# WeightPuzzle.net
KiCad netlist of a schematic drawn in Altium Designer
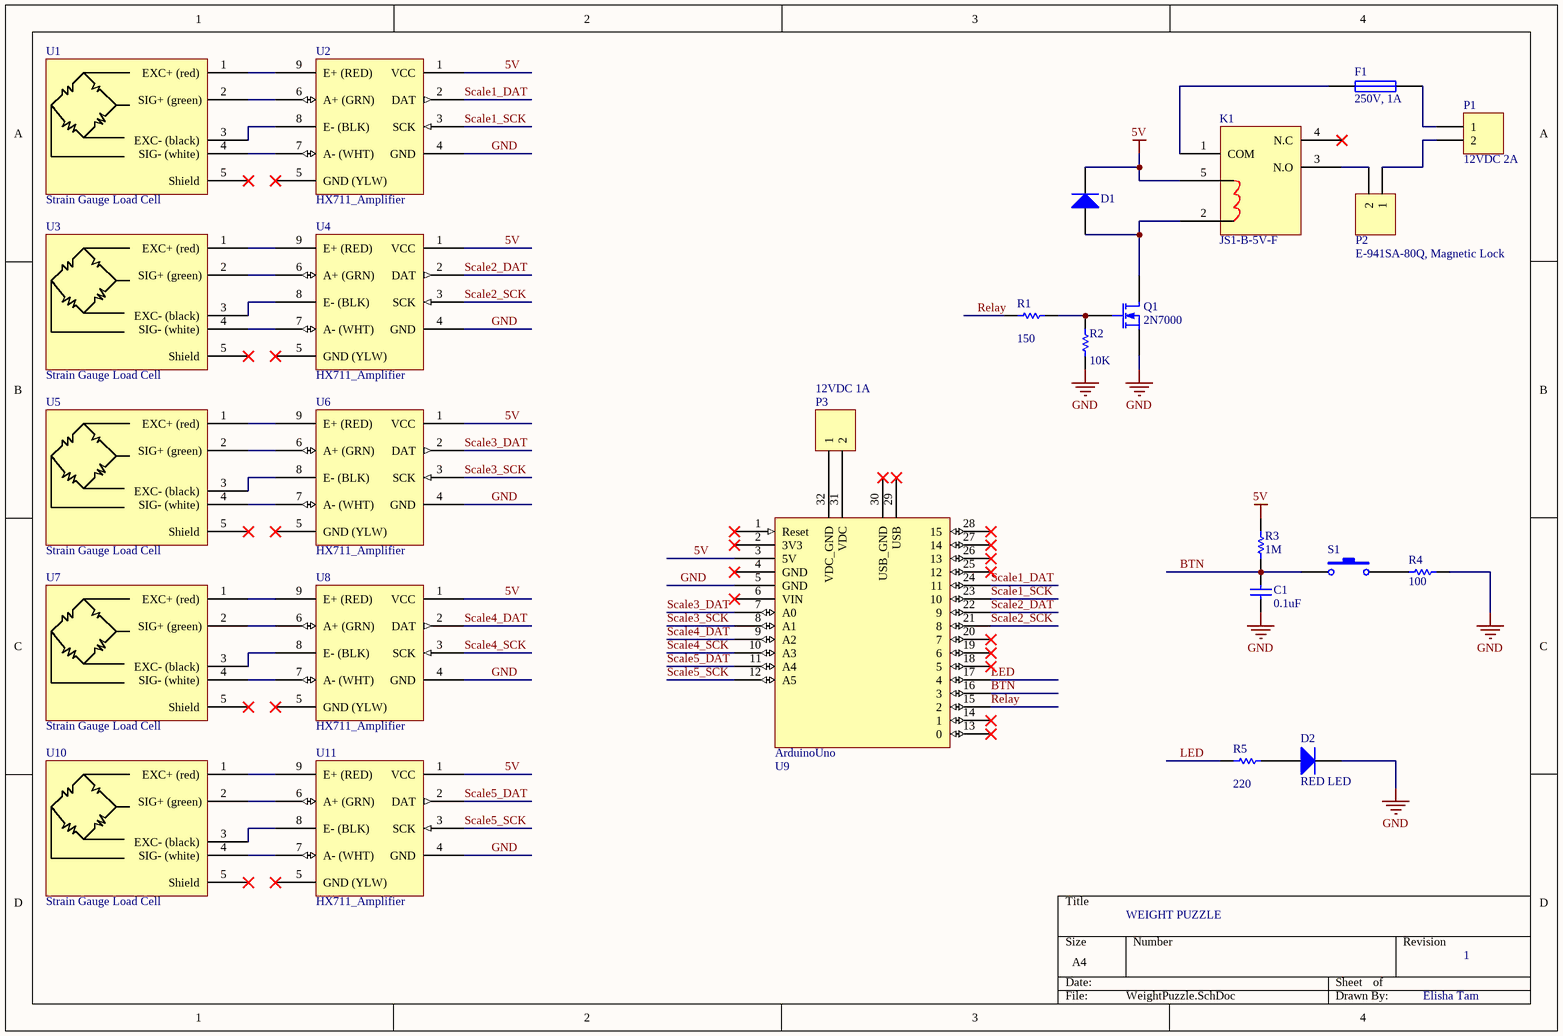
[diagram p0: WeightPuzzle.SchDoc]

(export (version "E")
  (design (tool "Eeschema 10.0.6"))
  (components
    (comp (ref "C1")
      (value "0.1uF")
      (footprint "RAD-0.3")
      (description "Capacitor")
      (fields (field (name "PUBLISHER") "Altium Limited"))
      (libsource (lib "Miscellaneous Devices") (part "Cap"))
    )
    (comp (ref "D1")
      (value "Diode")
      (footprint "SMC")
      (description "Default Diode")
      (fields (field (name "PUBLISHER") "Altium Limited"))
      (libsource (lib "Miscellaneous Devices") (part "Diode"))
    )
    (comp (ref "D2")
      (value "RED LED")
      (footprint "SMC")
      (description "Default Diode")
      (fields (field (name "PUBLISHER") "Altium Limited"))
      (libsource (lib "Miscellaneous Devices") (part "Diode"))
    )
    (comp (ref "F1")
      (value "250V, 1A")
      (footprint "PIN-W2/E2.8")
      (description "Fuse")
      (fields (field (name "PUBLISHER") "Altium Limited"))
      (libsource (lib "Miscellaneous Devices") (part "Fuse 1"))
    )
    (comp (ref "K1")
      (value "JS1-B-5V-F")
      (description "SPDT Relay 10A250VAC 10A 125VAC 5V")
      (libsource (lib "ElishaComponentsAltiumLibrary") (part "JS1-B-5V-F"))
    )
    (comp (ref "P1")
      (value "12VDC 2A")
      (footprint "HDR1X2")
      (description "Header, 2-Pin")
      (fields (field (name "PUBLISHER") "Altium Limited"))
      (libsource (lib "Miscellaneous Connectors") (part "Header 2"))
    )
    (comp (ref "P2")
      (value "E-941SA-80Q, Magnetic Lock")
      (footprint "HDR1X2")
      (description "Seco-Larm E-941SA-80Q Mini Maglock, 80 lb.")
      (fields (field (name "PUBLISHER") "Altium Limited"))
      (libsource (lib "") (part "Header 2_2"))
    )
    (comp (ref "P3")
      (value "12VDC 1A")
      (footprint "HDR1X2")
      (description "12V DC Adapter")
      (fields (field (name "PUBLISHER") "Altium Limited"))
      (libsource (lib "") (part "Header 2_1"))
    )
    (comp (ref "Q1")
      (value "2N7000")
      (footprint "E3")
      (description "N-Channel MOSFET")
      (fields (field (name "PUBLISHER") "Altium Limited"))
      (libsource (lib "Miscellaneous Devices") (part "MOSFET-N"))
    )
    (comp (ref "R1")
      (value "150")
      (footprint "AXIAL-0.3")
      (description "Resistor")
      (fields (field (name "Comment") "Res1") (field (name "PUBLISHER") "Altium Limited"))
      (libsource (lib "Miscellaneous Devices") (part "Res1"))
    )
    (comp (ref "R2")
      (value "10K")
      (footprint "AXIAL-0.3")
      (description "Resistor")
      (fields (field (name "Comment") "Res1") (field (name "PUBLISHER") "Altium Limited"))
      (libsource (lib "Miscellaneous Devices") (part "Res1"))
    )
    (comp (ref "R3")
      (value "1M")
      (footprint "AXIAL-0.3")
      (description "Resistor")
      (fields (field (name "PUBLISHER") "Altium Limited"))
      (libsource (lib "Miscellaneous Devices") (part "Res1"))
    )
    (comp (ref "R4")
      (value "100")
      (footprint "AXIAL-0.3")
      (description "Resistor")
      (fields (field (name "PUBLISHER") "Altium Limited"))
      (libsource (lib "Miscellaneous Devices") (part "Res1"))
    )
    (comp (ref "R5")
      (value "220")
      (footprint "AXIAL-0.3")
      (description "Resistor")
      (fields (field (name "Comment") "Res1") (field (name "PUBLISHER") "Altium Limited"))
      (libsource (lib "Miscellaneous Devices") (part "Res1"))
    )
    (comp (ref "S1")
      (value "SW-PB")
      (footprint "SPST-2")
      (description "Switch")
      (fields (field (name "PUBLISHER") "Altium Limited"))
      (libsource (lib "Miscellaneous Devices") (part "SW-PB"))
    )
    (comp (ref "U1")
      (value "Strain Gauge Load Cell")
      (description "Parallel Beam Load Cell")
      (libsource (lib "ElishaComponentsAltiumLibrary") (part "TAL220"))
    )
    (comp (ref "U2")
      (value "HX711_Amplifier")
      (description "Load Cell Amplifier")
      (libsource (lib "ElishaComponentsAltiumLibrary") (part "HX711_IC"))
    )
    (comp (ref "U3")
      (value "Strain Gauge Load Cell")
      (description "Parallel Beam Load Cell")
      (libsource (lib "ElishaComponentsAltiumLibrary") (part "TAL220"))
    )
    (comp (ref "U4")
      (value "HX711_Amplifier")
      (description "Load Cell Amplifier")
      (libsource (lib "ElishaComponentsAltiumLibrary") (part "HX711_IC"))
    )
    (comp (ref "U5")
      (value "Strain Gauge Load Cell")
      (description "Parallel Beam Load Cell")
      (libsource (lib "ElishaComponentsAltiumLibrary") (part "TAL220"))
    )
    (comp (ref "U6")
      (value "HX711_Amplifier")
      (description "Load Cell Amplifier")
      (libsource (lib "ElishaComponentsAltiumLibrary") (part "HX711_IC"))
    )
    (comp (ref "U7")
      (value "Strain Gauge Load Cell")
      (description "Parallel Beam Load Cell")
      (libsource (lib "ElishaComponentsAltiumLibrary") (part "TAL220"))
    )
    (comp (ref "U8")
      (value "HX711_Amplifier")
      (description "Load Cell Amplifier")
      (libsource (lib "ElishaComponentsAltiumLibrary") (part "HX711_IC"))
    )
    (comp (ref "U9")
      (value "ArduinoUno")
      (description "Arduino Uno Development Board")
      (libsource (lib "ElishaComponentsAltiumLibrary") (part "ArduinoUno"))
    )
    (comp (ref "U10")
      (value "Strain Gauge Load Cell")
      (description "Parallel Beam Load Cell")
      (libsource (lib "ElishaComponentsAltiumLibrary") (part "TAL220"))
    )
    (comp (ref "U11")
      (value "HX711_Amplifier")
      (description "Load Cell Amplifier")
      (libsource (lib "ElishaComponentsAltiumLibrary") (part "HX711_IC"))
    )
  )
  (nets
    (net (code "1") (name "/BTN") (class "Default")
      (node (ref "C1") (pin "1") (pinfunction "1_1") (pintype "passive"))
      (node (ref "R3") (pin "1") (pinfunction "1_1") (pintype "passive"))
      (node (ref "S1") (pin "1") (pinfunction "1_1") (pintype "passive"))
      (node (ref "U9") (pin "16") (pinfunction "3_16") (pintype "bidirectional"))
    )
    (net (code "2") (name "/LED") (class "Default")
      (node (ref "R5") (pin "2") (pinfunction "2_2") (pintype "passive"))
      (node (ref "U9") (pin "17") (pinfunction "4_17") (pintype "bidirectional"))
    )
    (net (code "3") (name "/Relay") (class "Default")
      (node (ref "R1") (pin "2") (pinfunction "2_2") (pintype "passive"))
      (node (ref "U9") (pin "15") (pinfunction "2_15") (pintype "bidirectional"))
    )
    (net (code "4") (name "/Scale1_DAT") (class "Default")
      (node (ref "U2") (pin "2") (pinfunction "DAT_2") (pintype "output"))
      (node (ref "U9") (pin "24") (pinfunction "11_24") (pintype "bidirectional"))
    )
    (net (code "5") (name "/Scale1_SCK") (class "Default")
      (node (ref "U2") (pin "3") (pinfunction "SCK_3") (pintype "input"))
      (node (ref "U9") (pin "23") (pinfunction "10_23") (pintype "bidirectional"))
    )
    (net (code "6") (name "/Scale2_DAT") (class "Default")
      (node (ref "U4") (pin "2") (pinfunction "DAT_2") (pintype "output"))
      (node (ref "U9") (pin "22") (pinfunction "9_22") (pintype "bidirectional"))
    )
    (net (code "7") (name "/Scale2_SCK") (class "Default")
      (node (ref "U4") (pin "3") (pinfunction "SCK_3") (pintype "input"))
      (node (ref "U9") (pin "21") (pinfunction "8_21") (pintype "bidirectional"))
    )
    (net (code "8") (name "/Scale3_DAT") (class "Default")
      (node (ref "U6") (pin "2") (pinfunction "DAT_2") (pintype "output"))
      (node (ref "U9") (pin "7") (pinfunction "A0_7") (pintype "bidirectional"))
    )
    (net (code "9") (name "/Scale3_SCK") (class "Default")
      (node (ref "U6") (pin "3") (pinfunction "SCK_3") (pintype "input"))
      (node (ref "U9") (pin "8") (pinfunction "A1_8") (pintype "bidirectional"))
    )
    (net (code "10") (name "/Scale4_DAT") (class "Default")
      (node (ref "U8") (pin "2") (pinfunction "DAT_2") (pintype "output"))
      (node (ref "U9") (pin "9") (pinfunction "A2_9") (pintype "bidirectional"))
    )
    (net (code "11") (name "/Scale4_SCK") (class "Default")
      (node (ref "U8") (pin "3") (pinfunction "SCK_3") (pintype "input"))
      (node (ref "U9") (pin "10") (pinfunction "A3_10") (pintype "bidirectional"))
    )
    (net (code "12") (name "/Scale5_DAT") (class "Default")
      (node (ref "U11") (pin "2") (pinfunction "DAT_2") (pintype "output"))
      (node (ref "U9") (pin "11") (pinfunction "A4_11") (pintype "bidirectional"))
    )
    (net (code "13") (name "/Scale5_SCK") (class "Default")
      (node (ref "U11") (pin "3") (pinfunction "SCK_3") (pintype "input"))
      (node (ref "U9") (pin "12") (pinfunction "A5_12") (pintype "bidirectional"))
    )
    (net (code "14") (name "5V") (class "Default")
      (node (ref "D1") (pin "2") (pinfunction "K_2") (pintype "passive"))
      (node (ref "K1") (pin "5") (pinfunction "5_5") (pintype "power_in"))
      (node (ref "R3") (pin "2") (pinfunction "2_2") (pintype "passive"))
      (node (ref "U11") (pin "1") (pinfunction "VCC_1") (pintype "power_in"))
      (node (ref "U2") (pin "1") (pinfunction "VCC_1") (pintype "power_in"))
      (node (ref "U4") (pin "1") (pinfunction "VCC_1") (pintype "power_in"))
      (node (ref "U6") (pin "1") (pinfunction "VCC_1") (pintype "power_in"))
      (node (ref "U8") (pin "1") (pinfunction "VCC_1") (pintype "power_in"))
      (node (ref "U9") (pin "3") (pinfunction "5V_3") (pintype "power_in"))
    )
    (net (code "15") (name "GND") (class "Default")
      (node (ref "C1") (pin "2") (pinfunction "2_2") (pintype "passive"))
      (node (ref "D2") (pin "2") (pinfunction "K_2") (pintype "passive"))
      (node (ref "Q1") (pin "3") (pinfunction "S_3") (pintype "passive"))
      (node (ref "R2") (pin "1") (pinfunction "1_1") (pintype "passive"))
      (node (ref "R4") (pin "1") (pinfunction "1_1") (pintype "passive"))
      (node (ref "U11") (pin "4") (pinfunction "GND_4") (pintype "power_in"))
      (node (ref "U2") (pin "4") (pinfunction "GND_4") (pintype "power_in"))
      (node (ref "U4") (pin "4") (pinfunction "GND_4") (pintype "power_in"))
      (node (ref "U6") (pin "4") (pinfunction "GND_4") (pintype "power_in"))
      (node (ref "U8") (pin "4") (pinfunction "GND_4") (pintype "power_in"))
      (node (ref "U9") (pin "5") (pinfunction "GND_5") (pintype "power_in"))
    )
    (net (code "16") (name "Net-(D1-A)") (class "Default")
      (node (ref "D1") (pin "1") (pinfunction "A_1") (pintype "passive"))
      (node (ref "K1") (pin "2") (pinfunction "2_2") (pintype "power_in"))
      (node (ref "Q1") (pin "1") (pinfunction "D_1") (pintype "passive"))
    )
    (net (code "17") (name "Net-(D2-A)") (class "Default")
      (node (ref "D2") (pin "1") (pinfunction "A_1") (pintype "passive"))
      (node (ref "R5") (pin "1") (pinfunction "1_1") (pintype "passive"))
    )
    (net (code "18") (name "Net-(F1-Pad2)") (class "Default")
      (node (ref "F1") (pin "2") (pinfunction "2_2") (pintype "passive"))
      (node (ref "P1") (pin "1") (pinfunction "1_1") (pintype "passive"))
    )
    (net (code "19") (name "Net-(K1-COM)") (class "Default")
      (node (ref "F1") (pin "1") (pinfunction "1_1") (pintype "passive"))
      (node (ref "K1") (pin "1") (pinfunction "COM_1") (pintype "power_in"))
    )
    (net (code "20") (name "Net-(K1-N.O)") (class "Default")
      (node (ref "K1") (pin "3") (pinfunction "N.O_3") (pintype "power_in"))
      (node (ref "P2") (pin "2") (pinfunction "2_2") (pintype "passive"))
    )
    (net (code "21") (name "Net-(P1-Pad2)") (class "Default")
      (node (ref "P1") (pin "2") (pinfunction "2_2") (pintype "passive"))
      (node (ref "P2") (pin "1") (pinfunction "1_1") (pintype "passive"))
    )
    (net (code "22") (name "Net-(Q1-G)") (class "Default")
      (node (ref "Q1") (pin "2") (pinfunction "G_2") (pintype "passive"))
      (node (ref "R1") (pin "1") (pinfunction "1_1") (pintype "passive"))
      (node (ref "R2") (pin "2") (pinfunction "2_2") (pintype "passive"))
    )
    (net (code "23") (name "Net-(R4-Pad2)") (class "Default")
      (node (ref "R4") (pin "2") (pinfunction "2_2") (pintype "passive"))
      (node (ref "S1") (pin "2") (pinfunction "2_2") (pintype "passive"))
    )
    (net (code "24") (name "Net-(U1-EXC+_(red))") (class "Default")
      (node (ref "U1") (pin "1") (pinfunction "EXC+_(red)_1") (pintype "power_in"))
      (node (ref "U2") (pin "9") (pinfunction "E+_(RED)_9") (pintype "power_in"))
    )
    (net (code "25") (name "Net-(U1-EXC-_(black))") (class "Default")
      (node (ref "U1") (pin "3") (pinfunction "EXC-_(black)_3") (pintype "power_in"))
      (node (ref "U2") (pin "8") (pinfunction "E-_(BLK)_8") (pintype "power_in"))
    )
    (net (code "26") (name "Net-(U1-SIG+_(green))") (class "Default")
      (node (ref "U1") (pin "2") (pinfunction "SIG+_(green)_2") (pintype "power_in"))
      (node (ref "U2") (pin "6") (pinfunction "A+_(GRN)_6") (pintype "bidirectional"))
    )
    (net (code "27") (name "Net-(U1-SIG-_(white))") (class "Default")
      (node (ref "U1") (pin "4") (pinfunction "SIG-_(white)_4") (pintype "power_in"))
      (node (ref "U2") (pin "7") (pinfunction "A-_(WHT)_7") (pintype "bidirectional"))
    )
    (net (code "28") (name "Net-(U3-EXC+_(red))") (class "Default")
      (node (ref "U3") (pin "1") (pinfunction "EXC+_(red)_1") (pintype "power_in"))
      (node (ref "U4") (pin "9") (pinfunction "E+_(RED)_9") (pintype "power_in"))
    )
    (net (code "29") (name "Net-(U3-EXC-_(black))") (class "Default")
      (node (ref "U3") (pin "3") (pinfunction "EXC-_(black)_3") (pintype "power_in"))
      (node (ref "U4") (pin "8") (pinfunction "E-_(BLK)_8") (pintype "power_in"))
    )
    (net (code "30") (name "Net-(U3-SIG+_(green))") (class "Default")
      (node (ref "U3") (pin "2") (pinfunction "SIG+_(green)_2") (pintype "power_in"))
      (node (ref "U4") (pin "6") (pinfunction "A+_(GRN)_6") (pintype "bidirectional"))
    )
    (net (code "31") (name "Net-(U3-SIG-_(white))") (class "Default")
      (node (ref "U3") (pin "4") (pinfunction "SIG-_(white)_4") (pintype "power_in"))
      (node (ref "U4") (pin "7") (pinfunction "A-_(WHT)_7") (pintype "bidirectional"))
    )
    (net (code "32") (name "Net-(U5-EXC+_(red))") (class "Default")
      (node (ref "U5") (pin "1") (pinfunction "EXC+_(red)_1") (pintype "power_in"))
      (node (ref "U6") (pin "9") (pinfunction "E+_(RED)_9") (pintype "power_in"))
    )
    (net (code "33") (name "Net-(U5-EXC-_(black))") (class "Default")
      (node (ref "U5") (pin "3") (pinfunction "EXC-_(black)_3") (pintype "power_in"))
      (node (ref "U6") (pin "8") (pinfunction "E-_(BLK)_8") (pintype "power_in"))
    )
    (net (code "34") (name "Net-(U5-SIG+_(green))") (class "Default")
      (node (ref "U5") (pin "2") (pinfunction "SIG+_(green)_2") (pintype "power_in"))
      (node (ref "U6") (pin "6") (pinfunction "A+_(GRN)_6") (pintype "bidirectional"))
    )
    (net (code "35") (name "Net-(U5-SIG-_(white))") (class "Default")
      (node (ref "U5") (pin "4") (pinfunction "SIG-_(white)_4") (pintype "power_in"))
      (node (ref "U6") (pin "7") (pinfunction "A-_(WHT)_7") (pintype "bidirectional"))
    )
    (net (code "36") (name "Net-(U7-EXC+_(red))") (class "Default")
      (node (ref "U7") (pin "1") (pinfunction "EXC+_(red)_1") (pintype "power_in"))
      (node (ref "U8") (pin "9") (pinfunction "E+_(RED)_9") (pintype "power_in"))
    )
    (net (code "37") (name "Net-(U7-EXC-_(black))") (class "Default")
      (node (ref "U7") (pin "3") (pinfunction "EXC-_(black)_3") (pintype "power_in"))
      (node (ref "U8") (pin "8") (pinfunction "E-_(BLK)_8") (pintype "power_in"))
    )
    (net (code "38") (name "Net-(U7-SIG+_(green))") (class "Default")
      (node (ref "U7") (pin "2") (pinfunction "SIG+_(green)_2") (pintype "power_in"))
      (node (ref "U8") (pin "6") (pinfunction "A+_(GRN)_6") (pintype "bidirectional"))
    )
    (net (code "39") (name "Net-(U7-SIG-_(white))") (class "Default")
      (node (ref "U7") (pin "4") (pinfunction "SIG-_(white)_4") (pintype "power_in"))
      (node (ref "U8") (pin "7") (pinfunction "A-_(WHT)_7") (pintype "bidirectional"))
    )
    (net (code "40") (name "Net-(U9-VDC)") (class "Default")
      (node (ref "P3") (pin "2") (pinfunction "2_2") (pintype "passive"))
      (node (ref "U9") (pin "31") (pinfunction "VDC_31") (pintype "power_in"))
    )
    (net (code "41") (name "Net-(U9-VDC_GND)") (class "Default")
      (node (ref "P3") (pin "1") (pinfunction "1_1") (pintype "passive"))
      (node (ref "U9") (pin "32") (pinfunction "VDC_GND_32") (pintype "power_in"))
    )
    (net (code "42") (name "Net-(U10-EXC+_(red))") (class "Default")
      (node (ref "U10") (pin "1") (pinfunction "EXC+_(red)_1") (pintype "power_in"))
      (node (ref "U11") (pin "9") (pinfunction "E+_(RED)_9") (pintype "power_in"))
    )
    (net (code "43") (name "Net-(U10-EXC-_(black))") (class "Default")
      (node (ref "U10") (pin "3") (pinfunction "EXC-_(black)_3") (pintype "power_in"))
      (node (ref "U11") (pin "8") (pinfunction "E-_(BLK)_8") (pintype "power_in"))
    )
    (net (code "44") (name "Net-(U10-SIG+_(green))") (class "Default")
      (node (ref "U10") (pin "2") (pinfunction "SIG+_(green)_2") (pintype "power_in"))
      (node (ref "U11") (pin "6") (pinfunction "A+_(GRN)_6") (pintype "bidirectional"))
    )
    (net (code "45") (name "Net-(U10-SIG-_(white))") (class "Default")
      (node (ref "U10") (pin "4") (pinfunction "SIG-_(white)_4") (pintype "power_in"))
      (node (ref "U11") (pin "7") (pinfunction "A-_(WHT)_7") (pintype "bidirectional"))
    )
    (net (code "46") (name "unconnected-(K1-N.C-Pad4)") (class "Default")
      (node (ref "K1") (pin "4") (pinfunction "N.C_4") (pintype "power_in+no_connect"))
    )
    (net (code "47") (name "unconnected-(U1-Shield-Pad5)") (class "Default")
      (node (ref "U1") (pin "5") (pinfunction "Shield_5") (pintype "passive+no_connect"))
    )
    (net (code "48") (name "unconnected-(U2-GND_(YLW)-Pad5)") (class "Default")
      (node (ref "U2") (pin "5") (pinfunction "GND_(YLW)_5") (pintype "power_in+no_connect"))
    )
    (net (code "49") (name "unconnected-(U3-Shield-Pad5)") (class "Default")
      (node (ref "U3") (pin "5") (pinfunction "Shield_5") (pintype "passive+no_connect"))
    )
    (net (code "50") (name "unconnected-(U4-GND_(YLW)-Pad5)") (class "Default")
      (node (ref "U4") (pin "5") (pinfunction "GND_(YLW)_5") (pintype "power_in+no_connect"))
    )
    (net (code "51") (name "unconnected-(U5-Shield-Pad5)") (class "Default")
      (node (ref "U5") (pin "5") (pinfunction "Shield_5") (pintype "passive+no_connect"))
    )
    (net (code "52") (name "unconnected-(U6-GND_(YLW)-Pad5)") (class "Default")
      (node (ref "U6") (pin "5") (pinfunction "GND_(YLW)_5") (pintype "power_in+no_connect"))
    )
    (net (code "53") (name "unconnected-(U7-Shield-Pad5)") (class "Default")
      (node (ref "U7") (pin "5") (pinfunction "Shield_5") (pintype "passive+no_connect"))
    )
    (net (code "54") (name "unconnected-(U8-GND_(YLW)-Pad5)") (class "Default")
      (node (ref "U8") (pin "5") (pinfunction "GND_(YLW)_5") (pintype "power_in+no_connect"))
    )
    (net (code "55") (name "unconnected-(U9-0-Pad13)") (class "Default")
      (node (ref "U9") (pin "13") (pinfunction "0_13") (pintype "bidirectional+no_connect"))
    )
    (net (code "56") (name "unconnected-(U9-1-Pad14)") (class "Default")
      (node (ref "U9") (pin "14") (pinfunction "1_14") (pintype "bidirectional+no_connect"))
    )
    (net (code "57") (name "unconnected-(U9-3V3-Pad2)") (class "Default")
      (node (ref "U9") (pin "2") (pinfunction "3V3_2") (pintype "power_in+no_connect"))
    )
    (net (code "58") (name "unconnected-(U9-5-Pad18)") (class "Default")
      (node (ref "U9") (pin "18") (pinfunction "5_18") (pintype "bidirectional+no_connect"))
    )
    (net (code "59") (name "unconnected-(U9-6-Pad19)") (class "Default")
      (node (ref "U9") (pin "19") (pinfunction "6_19") (pintype "bidirectional+no_connect"))
    )
    (net (code "60") (name "unconnected-(U9-7-Pad20)") (class "Default")
      (node (ref "U9") (pin "20") (pinfunction "7_20") (pintype "bidirectional+no_connect"))
    )
    (net (code "61") (name "unconnected-(U9-12-Pad25)") (class "Default")
      (node (ref "U9") (pin "25") (pinfunction "12_25") (pintype "bidirectional+no_connect"))
    )
    (net (code "62") (name "unconnected-(U9-13-Pad26)") (class "Default")
      (node (ref "U9") (pin "26") (pinfunction "13_26") (pintype "bidirectional+no_connect"))
    )
    (net (code "63") (name "unconnected-(U9-14-Pad27)") (class "Default")
      (node (ref "U9") (pin "27") (pinfunction "14_27") (pintype "bidirectional+no_connect"))
    )
    (net (code "64") (name "unconnected-(U9-15-Pad28)") (class "Default")
      (node (ref "U9") (pin "28") (pinfunction "15_28") (pintype "bidirectional+no_connect"))
    )
    (net (code "65") (name "unconnected-(U9-GND-Pad4)") (class "Default")
      (node (ref "U9") (pin "4") (pinfunction "GND_4") (pintype "power_in+no_connect"))
    )
    (net (code "66") (name "unconnected-(U9-Reset-Pad1)") (class "Default")
      (node (ref "U9") (pin "1") (pinfunction "Reset_1") (pintype "input+no_connect"))
    )
    (net (code "67") (name "unconnected-(U9-USB-Pad29)") (class "Default")
      (node (ref "U9") (pin "29") (pinfunction "USB_29") (pintype "power_in+no_connect"))
    )
    (net (code "68") (name "unconnected-(U9-USB_GND-Pad30)") (class "Default")
      (node (ref "U9") (pin "30") (pinfunction "USB_GND_30") (pintype "power_in+no_connect"))
    )
    (net (code "69") (name "unconnected-(U9-VIN-Pad6)") (class "Default")
      (node (ref "U9") (pin "6") (pinfunction "VIN_6") (pintype "power_in+no_connect"))
    )
    (net (code "70") (name "unconnected-(U10-Shield-Pad5)") (class "Default")
      (node (ref "U10") (pin "5") (pinfunction "Shield_5") (pintype "passive+no_connect"))
    )
    (net (code "71") (name "unconnected-(U11-GND_(YLW)-Pad5)") (class "Default")
      (node (ref "U11") (pin "5") (pinfunction "GND_(YLW)_5") (pintype "power_in+no_connect"))
    )
  )
)
